# Main.net
KiCad netlist of a schematic drawn in Altium Designer
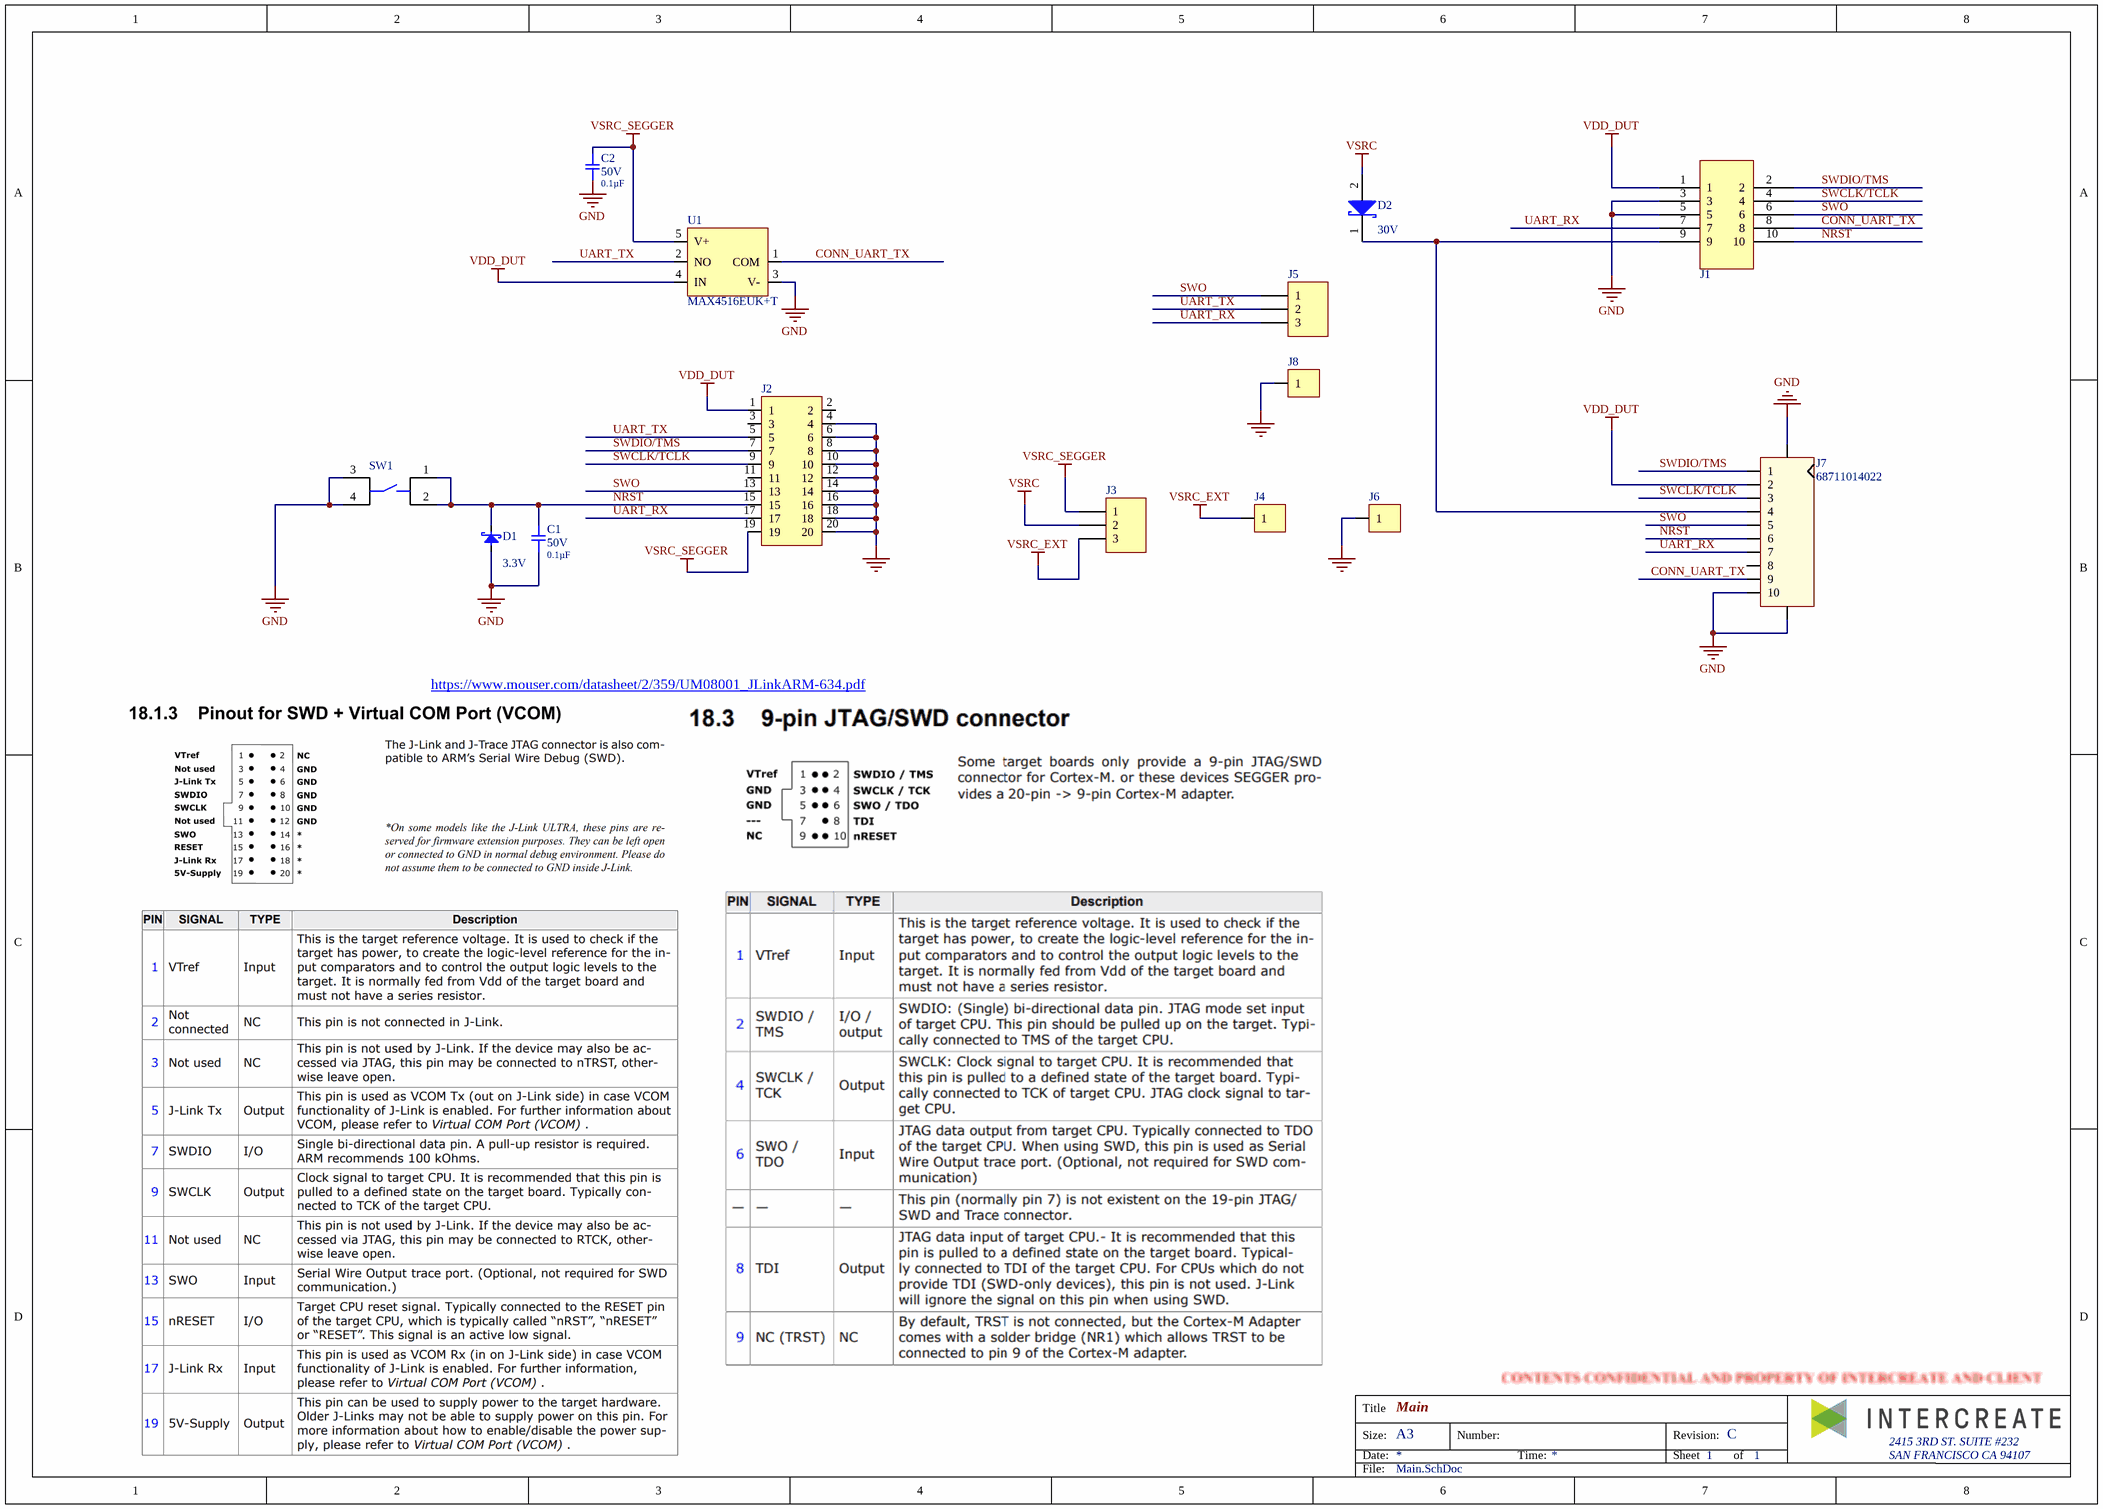
[diagram p0: Main.SchDoc]

(export (version "E")
  (design (tool "Eeschema 10.0.6"))
  (components
    (comp (ref "C1")
      (value "0.1µF")
      (footprint "CAP-0402")
      (description "CAP CER 0.1UF 50V X7R 0402 10%")
      (fields
        (field (name "TOLERANCE") "10%")
        (field (name "VOLTAGE RATING") "50V")
        (field (name "Comment") "GCM155R71H104KE02D")
      )
      (libsource (lib "intercreate") (part "CAP-0.1uF-50V-0402"))
    )
    (comp (ref "C2")
      (value "0.1µF")
      (footprint "CAP-0402")
      (description "CAP CER 0.1UF 50V X7R 0402 10%")
      (fields
        (field (name "TOLERANCE") "10%")
        (field (name "VOLTAGE RATING") "50V")
        (field (name "Comment") "GCM155R71H104KE02D")
      )
      (libsource (lib "intercreate") (part "CAP-0.1uF-50V-0402"))
    )
    (comp (ref "D1")
      (value "CPDQ3V3U-HF")
      (footprint "DIODE-SOD923f")
      (description "TVS DIODE 3.3V 10.4V SOD923F")
      (fields (field (name "REVERSE STANDOFF VOLTAGE") "3.3V"))
      (libsource (lib "intercreate") (part "DIODE-TVS-3.3V-SOD923F"))
    )
    (comp (ref "D2")
      (value "PMEG3010EP,115")
      (footprint "DIODE-SOD128")
      (description "DIODE SCHOTTKY 30V 1A SOD128")
      (fields (field (name "BASE PART NUMBER") "PMEG3010") (field (name "REVERSE VOLTAGE") "30V"))
      (libsource (lib "diodes") (part "DIODE-SCHOTTKY-30V-1A-SOD128"))
    )
    (comp (ref "J1")
      (value "FTSH-105-01-L-DV-K")
      (footprint "HDR-V-2X5-M")
      (description "CONN HEADER 10 POS DUAL .05\" SMD")
      (fields (field (name "MANUFACTURER") "Samtec"))
      (libsource (lib "intercreate") (part "HDR-V-2X5-M-JTAG"))
    )
    (comp (ref "J2")
      (value "SFH11-PBPC-D10-ST-BK")
      (footprint "HDR-V-2X10-F-2.54MM")
      (description "20 Position Header Connector 0.100\" (2.54mm) Through Hole Gold")
      (libsource (lib "intercreate") (part "HDR-V-2X10-F-2.54MM"))
    )
    (comp (ref "J3")
      (value "61300311121")
      (footprint "HDR-V-1X3")
      (description "Header, 3-Pin, 0.1\"")
      (fields (field (name "MANUFACTURER") "Wurth Electronics") (field (name "PUBLISHER") "Altium Limited"))
      (libsource (lib "intercreate") (part "HDR-V-1X3-M"))
    )
    (comp (ref "J4")
      (value "75160-101-01LF")
      (footprint "HDR-V-1X1-M")
      (libsource (lib "intercreate") (part "HDR-V-1X1-M"))
    )
    (comp (ref "J5")
      (value "61300311121")
      (footprint "HDR-V-1X3")
      (description "Header, 3-Pin, 0.1\"")
      (fields (field (name "MANUFACTURER") "Wurth Electronics") (field (name "PUBLISHER") "Altium Limited"))
      (libsource (lib "intercreate") (part "HDR-V-1X3-M"))
    )
    (comp (ref "J6")
      (value "75160-101-01LF")
      (footprint "HDR-V-1X1-M")
      (libsource (lib "intercreate") (part "HDR-V-1X1-M"))
    )
    (comp (ref "J7")
      (value "68711014022")
      (footprint "CONN-R-FPC-10P-WURTH")
      (description "CONN FFC FPC 10POS 0.50MM RA")
      (libsource (lib "intercreate") (part "CONN-R-FPC-10P-0.5MM-WURTH"))
    )
    (comp (ref "J8")
      (value "75160-101-01LF")
      (footprint "HDR-V-1X1-M")
      (libsource (lib "intercreate") (part "HDR-V-1X1-M"))
    )
    (comp (ref "SW1")
      (value "PTS645SK50SMTR92 LFS")
      (footprint "BTN-SPST-PTS645SK50SMTR92")
      (description "C & K COMPONENTS - PTS645SK50SMTR92LFS - SWITCH, SPST, 0.05A, 12VDC, SMD, 5MM")
      (libsource (lib "intercreate") (part "BTN-SPST-PTS645SK50SMTR92"))
    )
    (comp (ref "U1")
      (value "MAX4516EUK+T")
      (footprint "IC-SOT-23-5")
      (description "MAX4516 Series SPST-NO 6V 20 Ohm SMT Analog Switch - SOT-23")
      (libsource (lib "intercreate") (part "IC-SW-MAX4516"))
    )
  )
  (nets
    (net (code "1") (name "/CONN_UART_TX") (class "Default")
      (node (ref "J1") (pin "8") (pinfunction "8_8") (pintype "passive"))
      (node (ref "J7") (pin "9") (pinfunction "9_9") (pintype "passive"))
      (node (ref "U1") (pin "1") (pinfunction "COM_1") (pintype "passive"))
    )
    (net (code "2") (name "/NRST") (class "Default")
      (node (ref "C1") (pin "2") (pinfunction "2_2") (pintype "passive"))
      (node (ref "D1") (pin "1") (pinfunction "K_1") (pintype "passive"))
      (node (ref "J1") (pin "10") (pinfunction "10_10") (pintype "passive"))
      (node (ref "J2") (pin "15") (pinfunction "15_15") (pintype "passive"))
      (node (ref "J7") (pin "6") (pinfunction "6_6") (pintype "passive"))
      (node (ref "SW1") (pin "1") (pinfunction "1_1") (pintype "passive"))
      (node (ref "SW1") (pin "2") (pinfunction "2_2") (pintype "passive"))
    )
    (net (code "3") (name "/SWCLK{slash}TCLK") (class "Default")
      (node (ref "J1") (pin "4") (pinfunction "4_4") (pintype "passive"))
      (node (ref "J2") (pin "9") (pinfunction "9_9") (pintype "passive"))
      (node (ref "J7") (pin "3") (pinfunction "3_3") (pintype "passive"))
    )
    (net (code "4") (name "/SWDIO{slash}TMS") (class "Default")
      (node (ref "J1") (pin "2") (pinfunction "2_2") (pintype "passive"))
      (node (ref "J2") (pin "7") (pinfunction "7_7") (pintype "passive"))
      (node (ref "J7") (pin "1") (pinfunction "1_1") (pintype "passive"))
    )
    (net (code "5") (name "/SWO") (class "Default")
      (node (ref "J1") (pin "6") (pinfunction "6_6") (pintype "passive"))
      (node (ref "J2") (pin "13") (pinfunction "13_13") (pintype "passive"))
      (node (ref "J5") (pin "1") (pinfunction "1_1") (pintype "passive"))
      (node (ref "J7") (pin "5") (pinfunction "5_5") (pintype "passive"))
    )
    (net (code "6") (name "/UART_RX") (class "Default")
      (node (ref "J1") (pin "7") (pinfunction "7_7") (pintype "passive"))
      (node (ref "J2") (pin "17") (pinfunction "17_17") (pintype "passive"))
      (node (ref "J5") (pin "3") (pinfunction "3_3") (pintype "passive"))
      (node (ref "J7") (pin "7") (pinfunction "7_7") (pintype "passive"))
    )
    (net (code "7") (name "/UART_TX") (class "Default")
      (node (ref "J2") (pin "5") (pinfunction "5_5") (pintype "passive"))
      (node (ref "J5") (pin "2") (pinfunction "2_2") (pintype "passive"))
      (node (ref "U1") (pin "2") (pinfunction "NO_2") (pintype "passive"))
    )
    (net (code "8") (name "GND") (class "Default")
      (node (ref "C1") (pin "1") (pinfunction "1_1") (pintype "passive"))
      (node (ref "C2") (pin "1") (pinfunction "1_1") (pintype "passive"))
      (node (ref "D1") (pin "2") (pinfunction "A_2") (pintype "passive"))
      (node (ref "J1") (pin "3") (pinfunction "3_3") (pintype "passive"))
      (node (ref "J1") (pin "5") (pinfunction "5_5") (pintype "passive"))
      (node (ref "J2") (pin "10") (pinfunction "10_10") (pintype "passive"))
      (node (ref "J2") (pin "12") (pinfunction "12_12") (pintype "passive"))
      (node (ref "J2") (pin "14") (pinfunction "14_14") (pintype "passive"))
      (node (ref "J2") (pin "16") (pinfunction "16_16") (pintype "passive"))
      (node (ref "J2") (pin "18") (pinfunction "18_18") (pintype "passive"))
      (node (ref "J2") (pin "20") (pinfunction "20_20") (pintype "passive"))
      (node (ref "J2") (pin "4") (pinfunction "4_4") (pintype "passive"))
      (node (ref "J2") (pin "6") (pinfunction "6_6") (pintype "passive"))
      (node (ref "J2") (pin "8") (pinfunction "8_8") (pintype "passive"))
      (node (ref "J6") (pin "1") (pinfunction "1_1") (pintype "passive"))
      (node (ref "J7") (pin "10") (pinfunction "10_10") (pintype "passive"))
      (node (ref "J7") (pin "ME1") (pinfunction "ME1_ME1") (pintype "passive"))
      (node (ref "J7") (pin "ME2") (pinfunction "ME2_ME2") (pintype "passive"))
      (node (ref "J8") (pin "1") (pinfunction "1_1") (pintype "passive"))
      (node (ref "SW1") (pin "3") (pinfunction "3_3") (pintype "passive"))
      (node (ref "SW1") (pin "4") (pinfunction "4_4") (pintype "passive"))
      (node (ref "U1") (pin "3") (pinfunction "V-_3") (pintype "passive"))
    )
    (net (code "9") (name "Net-(D2-K)") (class "Default")
      (node (ref "D2") (pin "1") (pinfunction "K_1") (pintype "passive"))
      (node (ref "J1") (pin "9") (pinfunction "9_9") (pintype "passive"))
      (node (ref "J7") (pin "4") (pinfunction "4_4") (pintype "passive"))
    )
    (net (code "10") (name "VDD_DUT") (class "Default")
      (node (ref "J1") (pin "1") (pinfunction "1_1") (pintype "passive"))
      (node (ref "J2") (pin "1") (pinfunction "1_1") (pintype "passive"))
      (node (ref "J7") (pin "2") (pinfunction "2_2") (pintype "passive"))
      (node (ref "U1") (pin "4") (pinfunction "IN_4") (pintype "passive"))
    )
    (net (code "11") (name "VSRC") (class "Default")
      (node (ref "D2") (pin "2") (pinfunction "A_2") (pintype "passive"))
      (node (ref "J3") (pin "2") (pinfunction "2_2") (pintype "passive"))
    )
    (net (code "12") (name "VSRC_EXT") (class "Default")
      (node (ref "J3") (pin "3") (pinfunction "3_3") (pintype "passive"))
      (node (ref "J4") (pin "1") (pinfunction "1_1") (pintype "passive"))
    )
    (net (code "13") (name "VSRC_SEGGER") (class "Default")
      (node (ref "C2") (pin "2") (pinfunction "2_2") (pintype "passive"))
      (node (ref "J2") (pin "19") (pinfunction "19_19") (pintype "passive"))
      (node (ref "J3") (pin "1") (pinfunction "1_1") (pintype "passive"))
      (node (ref "U1") (pin "5") (pinfunction "V+_5") (pintype "passive"))
    )
    (net (code "14") (name "unconnected-(J2-Pad2)") (class "Default")
      (node (ref "J2") (pin "2") (pinfunction "2_2") (pintype "passive"))
    )
    (net (code "15") (name "unconnected-(J2-Pad3)") (class "Default")
      (node (ref "J2") (pin "3") (pinfunction "3_3") (pintype "passive"))
    )
    (net (code "16") (name "unconnected-(J2-Pad11)") (class "Default")
      (node (ref "J2") (pin "11") (pinfunction "11_11") (pintype "passive"))
    )
    (net (code "17") (name "unconnected-(J7-Pad8)") (class "Default")
      (node (ref "J7") (pin "8") (pinfunction "8_8") (pintype "passive"))
    )
  )
)
